# Digital_IP.net
KiCad netlist of a schematic drawn in Altium Designer
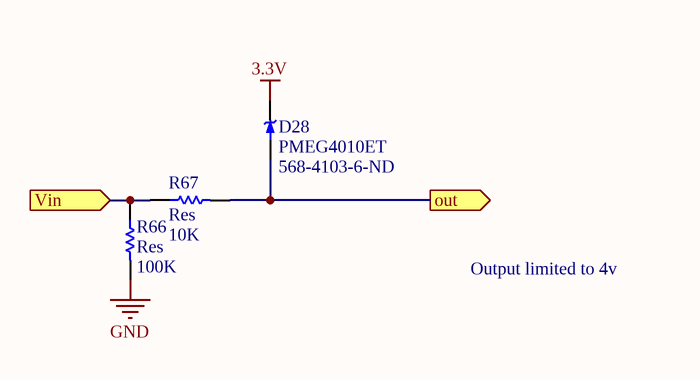
[diagram p0: Digital_IP.SchDoc]

(export (version "E")
  (design (tool "Eeschema 10.0.6"))
  (components
    (comp (ref "D28")
      (value "PMEG4010ET")
      (footprint "SOT23-3")
      (description "SCHOTTKY RECT 40V 1A SOT-23")
      (fields (field (name "SUPPLIER PART NUMBER 1") "568-4103-6-ND"))
      (libsource (lib "Diodes") (part "PMEG4010ET"))
    )
    (comp (ref "R66")
      (value "Res")
      (footprint "2012[0805]")
      (description "Surface Mount Resistor")
      (fields (field (name "ALTIUM_VALUE") "100K") (field (name "PUBLISHER") "Altium Limited"))
      (libsource (lib "Resistors") (part "Res"))
    )
    (comp (ref "R67")
      (value "Res")
      (footprint "2012[0805]")
      (description "Surface Mount Resistor")
      (fields (field (name "ALTIUM_VALUE") "10K") (field (name "PUBLISHER") "Altium Limited"))
      (libsource (lib "Resistors") (part "Res"))
    )
  )
  (nets
    (net (code "1") (name "/Vin") (class "Default")
      (node (ref "R66") (pin "1") (pinfunction "1_1") (pintype "passive"))
      (node (ref "R67") (pin "1") (pinfunction "1_1") (pintype "passive"))
    )
    (net (code "2") (name "/out") (class "Default")
      (node (ref "D28") (pin "1") (pinfunction "1_1") (pintype "passive"))
      (node (ref "R67") (pin "2") (pinfunction "2_2") (pintype "passive"))
    )
    (net (code "3") (name "3.3V") (class "Default")
      (node (ref "D28") (pin "3") (pinfunction "3_3") (pintype "passive"))
    )
    (net (code "4") (name "GND") (class "Default")
      (node (ref "R66") (pin "2") (pinfunction "2_2") (pintype "passive"))
    )
  )
)
